# drumsticks.net
KiCad netlist of a schematic drawn in Altium Designer
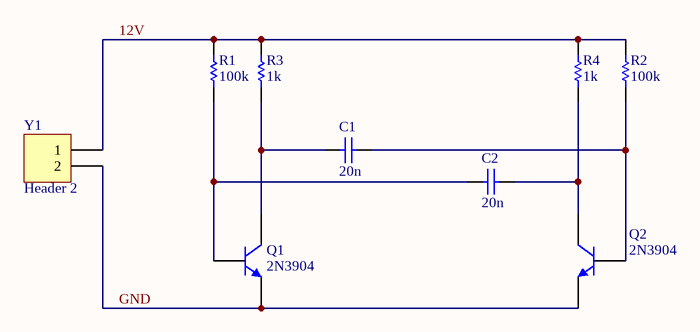
[diagram p0: drumsticks.SchDoc]

(export (version "E")
  (design (tool "Eeschema 10.0.6"))
  (components
    (comp (ref "C1")
      (value "20n")
      (footprint "RAD-0.3")
      (description "Capacitor")
      (fields (field (name "PUBLISHER") "Altium Limited"))
      (libsource (lib "Miscellaneous Devices") (part "Cap"))
    )
    (comp (ref "C2")
      (value "20n")
      (footprint "RAD-0.3")
      (description "Capacitor")
      (fields (field (name "PUBLISHER") "Altium Limited"))
      (libsource (lib "Miscellaneous Devices") (part "Cap"))
    )
    (comp (ref "Q1")
      (value "2N3904")
      (footprint "TO-92A")
      (description "NPN General Purpose Amplifier")
      (fields (field (name "PUBLISHER") "Altium Limited"))
      (libsource (lib "Miscellaneous Devices") (part "2N3904"))
    )
    (comp (ref "Q2")
      (value "2N3904")
      (footprint "TO-92A")
      (description "NPN General Purpose Amplifier")
      (fields (field (name "PUBLISHER") "Altium Limited"))
      (libsource (lib "Miscellaneous Devices") (part "2N3904"))
    )
    (comp (ref "R1")
      (value "100k")
      (footprint "AXIAL-0.3")
      (description "Resistor")
      (fields (field (name "PUBLISHER") "Altium Limited"))
      (libsource (lib "Miscellaneous Devices") (part "Res1"))
    )
    (comp (ref "R2")
      (value "100k")
      (footprint "AXIAL-0.3")
      (description "Resistor")
      (fields (field (name "PUBLISHER") "Altium Limited"))
      (libsource (lib "Miscellaneous Devices") (part "Res1"))
    )
    (comp (ref "R3")
      (value "1k")
      (footprint "AXIAL-0.3")
      (description "Resistor")
      (fields (field (name "PUBLISHER") "Altium Limited"))
      (libsource (lib "Miscellaneous Devices") (part "Res1"))
    )
    (comp (ref "R4")
      (value "1k")
      (footprint "AXIAL-0.3")
      (description "Resistor")
      (fields (field (name "PUBLISHER") "Altium Limited"))
      (libsource (lib "Miscellaneous Devices") (part "Res1"))
    )
    (comp (ref "Y1")
      (value "Header 2")
      (footprint "HDR1X2")
      (description "Header, 2-Pin")
      (fields (field (name "PUBLISHER") "Altium Limited"))
      (libsource (lib "Miscellaneous Connectors") (part "Header 2"))
    )
  )
  (nets
    (net (code "1") (name "/12V") (class "Default")
      (node (ref "R1") (pin "2") (pinfunction "2_2") (pintype "passive"))
      (node (ref "R2") (pin "2") (pinfunction "2_2") (pintype "passive"))
      (node (ref "R3") (pin "2") (pinfunction "2_2") (pintype "passive"))
      (node (ref "R4") (pin "2") (pinfunction "2_2") (pintype "passive"))
      (node (ref "Y1") (pin "1") (pinfunction "1_1") (pintype "passive"))
    )
    (net (code "2") (name "/GND") (class "Default")
      (node (ref "Q1") (pin "1") (pinfunction "E_1") (pintype "passive"))
      (node (ref "Q2") (pin "1") (pinfunction "E_1") (pintype "passive"))
      (node (ref "Y1") (pin "2") (pinfunction "2_2") (pintype "passive"))
    )
    (net (code "3") (name "Net-(Q1-B)") (class "Default")
      (node (ref "C2") (pin "1") (pinfunction "1_1") (pintype "passive"))
      (node (ref "Q1") (pin "2") (pinfunction "B_2") (pintype "passive"))
      (node (ref "R1") (pin "1") (pinfunction "1_1") (pintype "passive"))
    )
    (net (code "4") (name "Net-(Q1-C)") (class "Default")
      (node (ref "C1") (pin "1") (pinfunction "1_1") (pintype "passive"))
      (node (ref "Q1") (pin "3") (pinfunction "C_3") (pintype "passive"))
      (node (ref "R3") (pin "1") (pinfunction "1_1") (pintype "passive"))
    )
    (net (code "5") (name "Net-(Q2-B)") (class "Default")
      (node (ref "C1") (pin "2") (pinfunction "2_2") (pintype "passive"))
      (node (ref "Q2") (pin "2") (pinfunction "B_2") (pintype "passive"))
      (node (ref "R2") (pin "1") (pinfunction "1_1") (pintype "passive"))
    )
    (net (code "6") (name "Net-(Q2-C)") (class "Default")
      (node (ref "C2") (pin "2") (pinfunction "2_2") (pintype "passive"))
      (node (ref "Q2") (pin "3") (pinfunction "C_3") (pintype "passive"))
      (node (ref "R4") (pin "1") (pinfunction "1_1") (pintype "passive"))
    )
  )
)
